# Connectors.net
KiCad netlist of a schematic drawn in Altium Designer
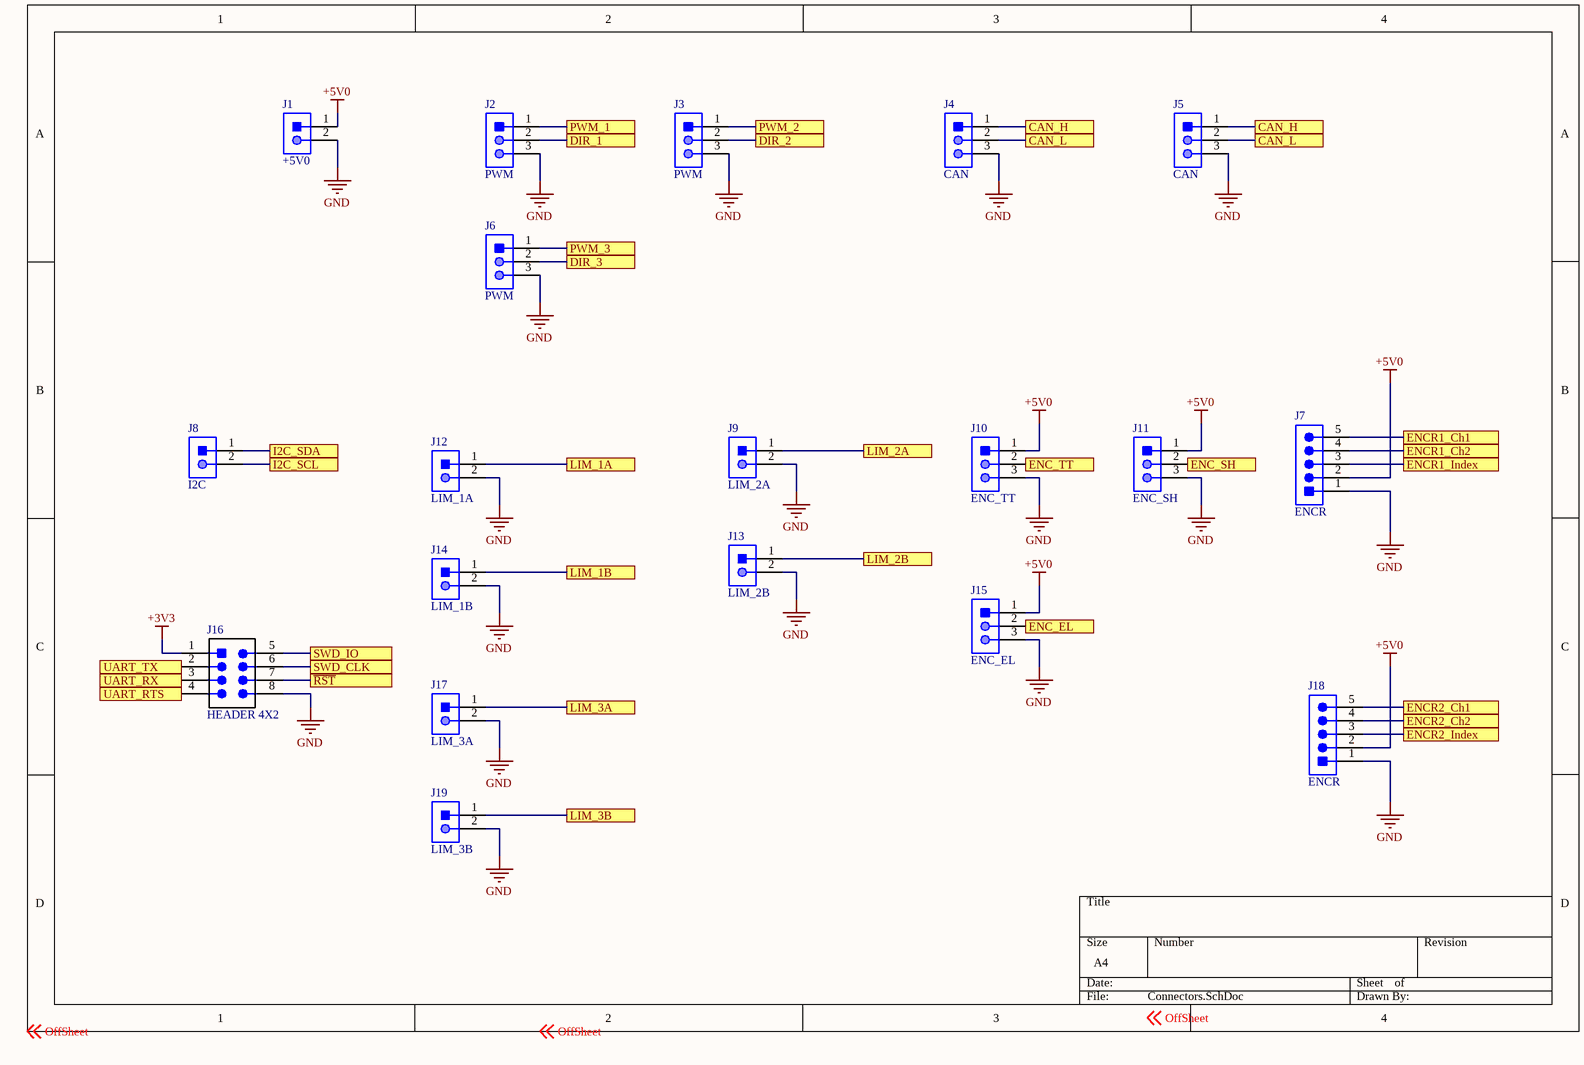
[diagram p0: Connectors.SchDoc]

(export (version "E")
  (design (tool "Eeschema 10.0.6"))
  (components
    (comp (ref "J1")
      (value "+5V0")
      (footprint "JST-B2B-SM4-TB")
      (description "CONN HEADER PH TOP 2POS 2MM SMD")
      (fields (field (name "MANUFACTURER") "JST") (field (name "MPN") "B2B-PH-SM4-TB"))
      (libsource (lib "UWRT_Schematic_Library_2019") (part "CON_2M_PH_TOP_SMT"))
    )
    (comp (ref "J2")
      (value "PWM")
      (footprint "JST-B3B-SM4-TB")
      (description "CONN HEADER PH TOP 3POS 2MM SMD")
      (fields (field (name "MANUFACTURER") "JST") (field (name "MPN") "B3B-PH-SM4-TB(LF)(SN)"))
      (libsource (lib "UWRT_Schematic_Library_2019") (part "CON_3M_PH_TOP_SMT"))
    )
    (comp (ref "J3")
      (value "PWM")
      (footprint "JST-B3B-SM4-TB")
      (description "CONN HEADER PH TOP 3POS 2MM SMD")
      (fields (field (name "MANUFACTURER") "JST") (field (name "MPN") "B3B-PH-SM4-TB(LF)(SN)"))
      (libsource (lib "UWRT_Schematic_Library_2019") (part "CON_3M_PH_TOP_SMT"))
    )
    (comp (ref "J4")
      (value "CAN")
      (footprint "JST-B3B-SM4-TB")
      (description "CONN HEADER PH TOP 3POS 2MM SMD")
      (fields (field (name "MANUFACTURER") "JST") (field (name "MPN") "B3B-PH-SM4-TB(LF)(SN)"))
      (libsource (lib "UWRT_Schematic_Library_2019") (part "CON_3M_PH_TOP_SMT"))
    )
    (comp (ref "J5")
      (value "CAN")
      (footprint "JST-B3B-SM4-TB")
      (description "CONN HEADER PH TOP 3POS 2MM SMD")
      (fields (field (name "MANUFACTURER") "JST") (field (name "MPN") "B3B-PH-SM4-TB(LF)(SN)"))
      (libsource (lib "UWRT_Schematic_Library_2019") (part "CON_3M_PH_TOP_SMT"))
    )
    (comp (ref "J6")
      (value "PWM")
      (footprint "JST-B3B-SM4-TB")
      (description "CONN HEADER PH TOP 3POS 2MM SMD")
      (fields (field (name "MANUFACTURER") "JST") (field (name "MPN") "B3B-PH-SM4-TB(LF)(SN)"))
      (libsource (lib "UWRT_Schematic_Library_2019") (part "CON_3M_PH_TOP_SMT"))
    )
    (comp (ref "J7")
      (value "ENCR")
      (footprint "JST-B5B-SM4-TB")
      (description "CONN HEADER PH TOP 5POS 2MM SMD")
      (fields (field (name "MANUFACTURER") "JST") (field (name "MPN") "B5B-PH-SM4-TB(LF)(SN)"))
      (libsource (lib "UWRT_Schematic_Library_2019") (part "CON_5M_PH_TOP_SMT"))
    )
    (comp (ref "J8")
      (value "I2C")
      (footprint "JST-B2B-SM4-TB")
      (description "CONN HEADER PH TOP 2POS 2MM SMD")
      (fields (field (name "MANUFACTURER") "JST") (field (name "MPN") "B2B-PH-SM4-TB"))
      (libsource (lib "UWRT_Schematic_Library_2019") (part "CON_2M_PH_TOP_SMT"))
    )
    (comp (ref "J9")
      (value "LIM_2A")
      (footprint "JST-B2B-SM4-TB")
      (description "CONN HEADER PH TOP 2POS 2MM SMD")
      (fields (field (name "MANUFACTURER") "JST") (field (name "MPN") "B2B-PH-SM4-TB"))
      (libsource (lib "UWRT_Schematic_Library_2019") (part "CON_2M_PH_TOP_SMT"))
    )
    (comp (ref "J10")
      (value "ENC_TT")
      (footprint "JST-B3B-SM4-TB")
      (description "CONN HEADER PH TOP 3POS 2MM SMD")
      (fields (field (name "MANUFACTURER") "JST") (field (name "MPN") "B3B-PH-SM4-TB(LF)(SN)"))
      (libsource (lib "UWRT_Schematic_Library_2019") (part "CON_3M_PH_TOP_SMT"))
    )
    (comp (ref "J11")
      (value "ENC_SH")
      (footprint "JST-B3B-SM4-TB")
      (description "CONN HEADER PH TOP 3POS 2MM SMD")
      (fields (field (name "MANUFACTURER") "JST") (field (name "MPN") "B3B-PH-SM4-TB(LF)(SN)"))
      (libsource (lib "UWRT_Schematic_Library_2019") (part "CON_3M_PH_TOP_SMT"))
    )
    (comp (ref "J12")
      (value "LIM_1A")
      (footprint "JST-B2B-SM4-TB")
      (description "CONN HEADER PH TOP 2POS 2MM SMD")
      (fields (field (name "MANUFACTURER") "JST") (field (name "MPN") "B2B-PH-SM4-TB"))
      (libsource (lib "UWRT_Schematic_Library_2019") (part "CON_2M_PH_TOP_SMT"))
    )
    (comp (ref "J13")
      (value "LIM_2B")
      (footprint "JST-B2B-SM4-TB")
      (description "CONN HEADER PH TOP 2POS 2MM SMD")
      (fields (field (name "MANUFACTURER") "JST") (field (name "MPN") "B2B-PH-SM4-TB"))
      (libsource (lib "UWRT_Schematic_Library_2019") (part "CON_2M_PH_TOP_SMT"))
    )
    (comp (ref "J14")
      (value "LIM_1B")
      (footprint "JST-B2B-SM4-TB")
      (description "CONN HEADER PH TOP 2POS 2MM SMD")
      (fields (field (name "MANUFACTURER") "JST") (field (name "MPN") "B2B-PH-SM4-TB"))
      (libsource (lib "UWRT_Schematic_Library_2019") (part "CON_2M_PH_TOP_SMT"))
    )
    (comp (ref "J15")
      (value "ENC_EL")
      (footprint "JST-B3B-SM4-TB")
      (description "CONN HEADER PH TOP 3POS 2MM SMD")
      (fields (field (name "MANUFACTURER") "JST") (field (name "MPN") "B3B-PH-SM4-TB(LF)(SN)"))
      (libsource (lib "UWRT_Schematic_Library_2019") (part "CON_3M_PH_TOP_SMT"))
    )
    (comp (ref "J16")
      (value "HEADER 4X2")
      (footprint "UWRT_Footprint_Library_2019:HEADER_2X4")
      (description "Header, 4-Pin Dual row")
      (fields (field (name "MPN") "GRPB042VWVN-RC") (field (name "DIGIKEY PART NUMBER") "S9015E-04-ND"))
      (libsource (lib "UWRT_Schematic_Library_2019") (part "HEADER 4X2"))
    )
    (comp (ref "J17")
      (value "LIM_3A")
      (footprint "JST-B2B-SM4-TB")
      (description "CONN HEADER PH TOP 2POS 2MM SMD")
      (fields (field (name "MANUFACTURER") "JST") (field (name "MPN") "B2B-PH-SM4-TB"))
      (libsource (lib "UWRT_Schematic_Library_2019") (part "CON_2M_PH_TOP_SMT"))
    )
    (comp (ref "J18")
      (value "ENCR")
      (footprint "JST-B5B-SM4-TB")
      (description "CONN HEADER PH TOP 5POS 2MM SMD")
      (fields (field (name "MANUFACTURER") "JST") (field (name "MPN") "B5B-PH-SM4-TB(LF)(SN)"))
      (libsource (lib "UWRT_Schematic_Library_2019") (part "CON_5M_PH_TOP_SMT"))
    )
    (comp (ref "J19")
      (value "LIM_3B")
      (footprint "JST-B2B-SM4-TB")
      (description "CONN HEADER PH TOP 2POS 2MM SMD")
      (fields (field (name "MANUFACTURER") "JST") (field (name "MPN") "B2B-PH-SM4-TB"))
      (libsource (lib "UWRT_Schematic_Library_2019") (part "CON_2M_PH_TOP_SMT"))
    )
  )
  (nets
    (net (code "1") (name "+3V3") (class "Default")
      (node (ref "J16") (pin "1") (pinfunction "VCC_1") (pintype "passive"))
    )
    (net (code "2") (name "+5V0") (class "Default")
      (node (ref "J1") (pin "1") (pinfunction "1_1") (pintype "passive"))
      (node (ref "J10") (pin "1") (pinfunction "1_1") (pintype "passive"))
      (node (ref "J11") (pin "1") (pinfunction "1_1") (pintype "passive"))
      (node (ref "J15") (pin "1") (pinfunction "1_1") (pintype "passive"))
      (node (ref "J18") (pin "2") (pinfunction "2_2") (pintype "passive"))
      (node (ref "J7") (pin "2") (pinfunction "2_2") (pintype "passive"))
    )
    (net (code "3") (name "/CAN_H") (class "Default")
      (node (ref "J4") (pin "1") (pinfunction "1_1") (pintype "passive"))
      (node (ref "J5") (pin "1") (pinfunction "1_1") (pintype "passive"))
    )
    (net (code "4") (name "/CAN_L") (class "Default")
      (node (ref "J4") (pin "2") (pinfunction "2_2") (pintype "passive"))
      (node (ref "J5") (pin "2") (pinfunction "2_2") (pintype "passive"))
    )
    (net (code "5") (name "/DIR_1") (class "Default")
      (node (ref "J2") (pin "2") (pinfunction "2_2") (pintype "passive"))
    )
    (net (code "6") (name "/DIR_2") (class "Default")
      (node (ref "J3") (pin "2") (pinfunction "2_2") (pintype "passive"))
    )
    (net (code "7") (name "/DIR_3") (class "Default")
      (node (ref "J6") (pin "2") (pinfunction "2_2") (pintype "passive"))
    )
    (net (code "8") (name "/ENCR1_Ch1") (class "Default")
      (node (ref "J7") (pin "5") (pinfunction "5_5") (pintype "passive"))
    )
    (net (code "9") (name "/ENCR1_Ch2") (class "Default")
      (node (ref "J7") (pin "4") (pinfunction "4_4") (pintype "passive"))
    )
    (net (code "10") (name "/ENCR1_Index") (class "Default")
      (node (ref "J7") (pin "3") (pinfunction "3_3") (pintype "passive"))
    )
    (net (code "11") (name "/ENCR2_Ch1") (class "Default")
      (node (ref "J18") (pin "5") (pinfunction "5_5") (pintype "passive"))
    )
    (net (code "12") (name "/ENCR2_Ch2") (class "Default")
      (node (ref "J18") (pin "4") (pinfunction "4_4") (pintype "passive"))
    )
    (net (code "13") (name "/ENCR2_Index") (class "Default")
      (node (ref "J18") (pin "3") (pinfunction "3_3") (pintype "passive"))
    )
    (net (code "14") (name "/ENC_EL") (class "Default")
      (node (ref "J15") (pin "2") (pinfunction "2_2") (pintype "passive"))
    )
    (net (code "15") (name "/ENC_SH") (class "Default")
      (node (ref "J11") (pin "2") (pinfunction "2_2") (pintype "passive"))
    )
    (net (code "16") (name "/ENC_TT") (class "Default")
      (node (ref "J10") (pin "2") (pinfunction "2_2") (pintype "passive"))
    )
    (net (code "17") (name "/I2C_SCL") (class "Default")
      (node (ref "J8") (pin "2") (pinfunction "2_2") (pintype "passive"))
    )
    (net (code "18") (name "/I2C_SDA") (class "Default")
      (node (ref "J8") (pin "1") (pinfunction "1_1") (pintype "passive"))
    )
    (net (code "19") (name "/LIM_1A") (class "Default")
      (node (ref "J12") (pin "1") (pinfunction "1_1") (pintype "passive"))
    )
    (net (code "20") (name "/LIM_1B") (class "Default")
      (node (ref "J14") (pin "1") (pinfunction "1_1") (pintype "passive"))
    )
    (net (code "21") (name "/LIM_2A") (class "Default")
      (node (ref "J9") (pin "1") (pinfunction "1_1") (pintype "passive"))
    )
    (net (code "22") (name "/LIM_2B") (class "Default")
      (node (ref "J13") (pin "1") (pinfunction "1_1") (pintype "passive"))
    )
    (net (code "23") (name "/LIM_3A") (class "Default")
      (node (ref "J17") (pin "1") (pinfunction "1_1") (pintype "passive"))
    )
    (net (code "24") (name "/LIM_3B") (class "Default")
      (node (ref "J19") (pin "1") (pinfunction "1_1") (pintype "passive"))
    )
    (net (code "25") (name "/PWM_1") (class "Default")
      (node (ref "J2") (pin "1") (pinfunction "1_1") (pintype "passive"))
    )
    (net (code "26") (name "/PWM_2") (class "Default")
      (node (ref "J3") (pin "1") (pinfunction "1_1") (pintype "passive"))
    )
    (net (code "27") (name "/PWM_3") (class "Default")
      (node (ref "J6") (pin "1") (pinfunction "1_1") (pintype "passive"))
    )
    (net (code "28") (name "/SWD_CLK") (class "Default")
      (node (ref "J16") (pin "6") (pinfunction "2_6") (pintype "passive"))
    )
    (net (code "29") (name "/SWD_IO") (class "Default")
      (node (ref "J16") (pin "5") (pinfunction "GND_5") (pintype "passive"))
    )
    (net (code "30") (name "/UART_RTS") (class "Default")
      (node (ref "J16") (pin "4") (pinfunction "4_4") (pintype "passive"))
    )
    (net (code "31") (name "/UART_RX") (class "Default")
      (node (ref "J16") (pin "3") (pinfunction "3_3") (pintype "passive"))
    )
    (net (code "32") (name "/UART_TX") (class "Default")
      (node (ref "J16") (pin "2") (pinfunction "2_2") (pintype "passive"))
    )
    (net (code "33") (name "/~{RST}") (class "Default")
      (node (ref "J16") (pin "7") (pinfunction "3_7") (pintype "passive"))
    )
    (net (code "34") (name "GND") (class "Default")
      (node (ref "J1") (pin "2") (pinfunction "2_2") (pintype "passive"))
      (node (ref "J10") (pin "3") (pinfunction "3_3") (pintype "passive"))
      (node (ref "J11") (pin "3") (pinfunction "3_3") (pintype "passive"))
      (node (ref "J12") (pin "2") (pinfunction "2_2") (pintype "passive"))
      (node (ref "J13") (pin "2") (pinfunction "2_2") (pintype "passive"))
      (node (ref "J14") (pin "2") (pinfunction "2_2") (pintype "passive"))
      (node (ref "J15") (pin "3") (pinfunction "3_3") (pintype "passive"))
      (node (ref "J16") (pin "8") (pinfunction "4_8") (pintype "passive"))
      (node (ref "J17") (pin "2") (pinfunction "2_2") (pintype "passive"))
      (node (ref "J18") (pin "1") (pinfunction "1_1") (pintype "passive"))
      (node (ref "J19") (pin "2") (pinfunction "2_2") (pintype "passive"))
      (node (ref "J2") (pin "3") (pinfunction "3_3") (pintype "passive"))
      (node (ref "J3") (pin "3") (pinfunction "3_3") (pintype "passive"))
      (node (ref "J4") (pin "3") (pinfunction "3_3") (pintype "passive"))
      (node (ref "J5") (pin "3") (pinfunction "3_3") (pintype "passive"))
      (node (ref "J6") (pin "3") (pinfunction "3_3") (pintype "passive"))
      (node (ref "J7") (pin "1") (pinfunction "1_1") (pintype "passive"))
      (node (ref "J9") (pin "2") (pinfunction "2_2") (pintype "passive"))
    )
  )
)
